# zigbee_iNEMO.net
KiCad netlist of a schematic drawn in EAGLE
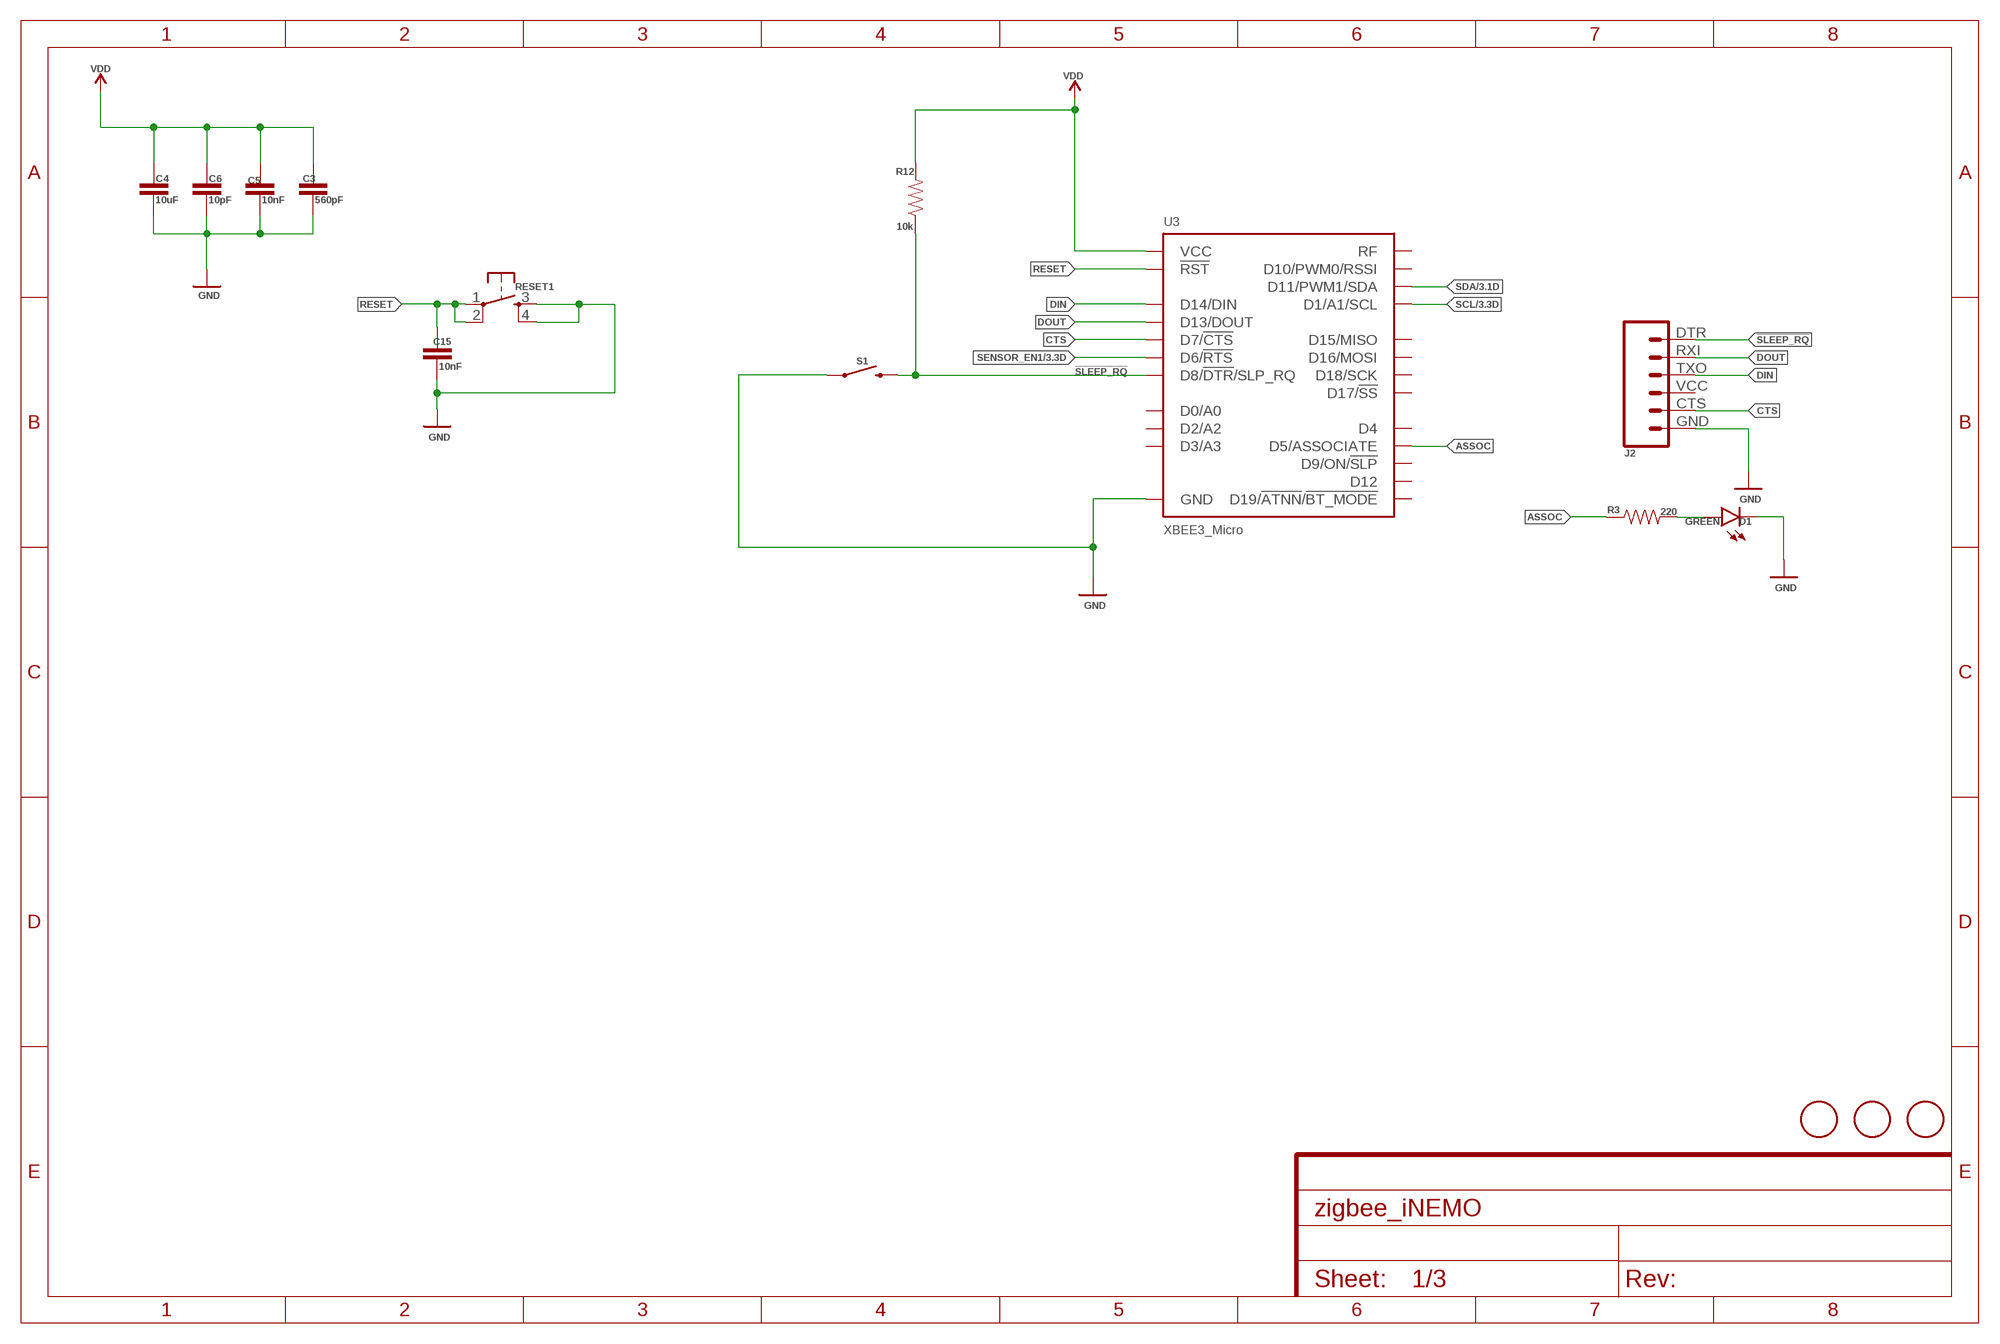
[diagram p0: schematic, sheet 1]
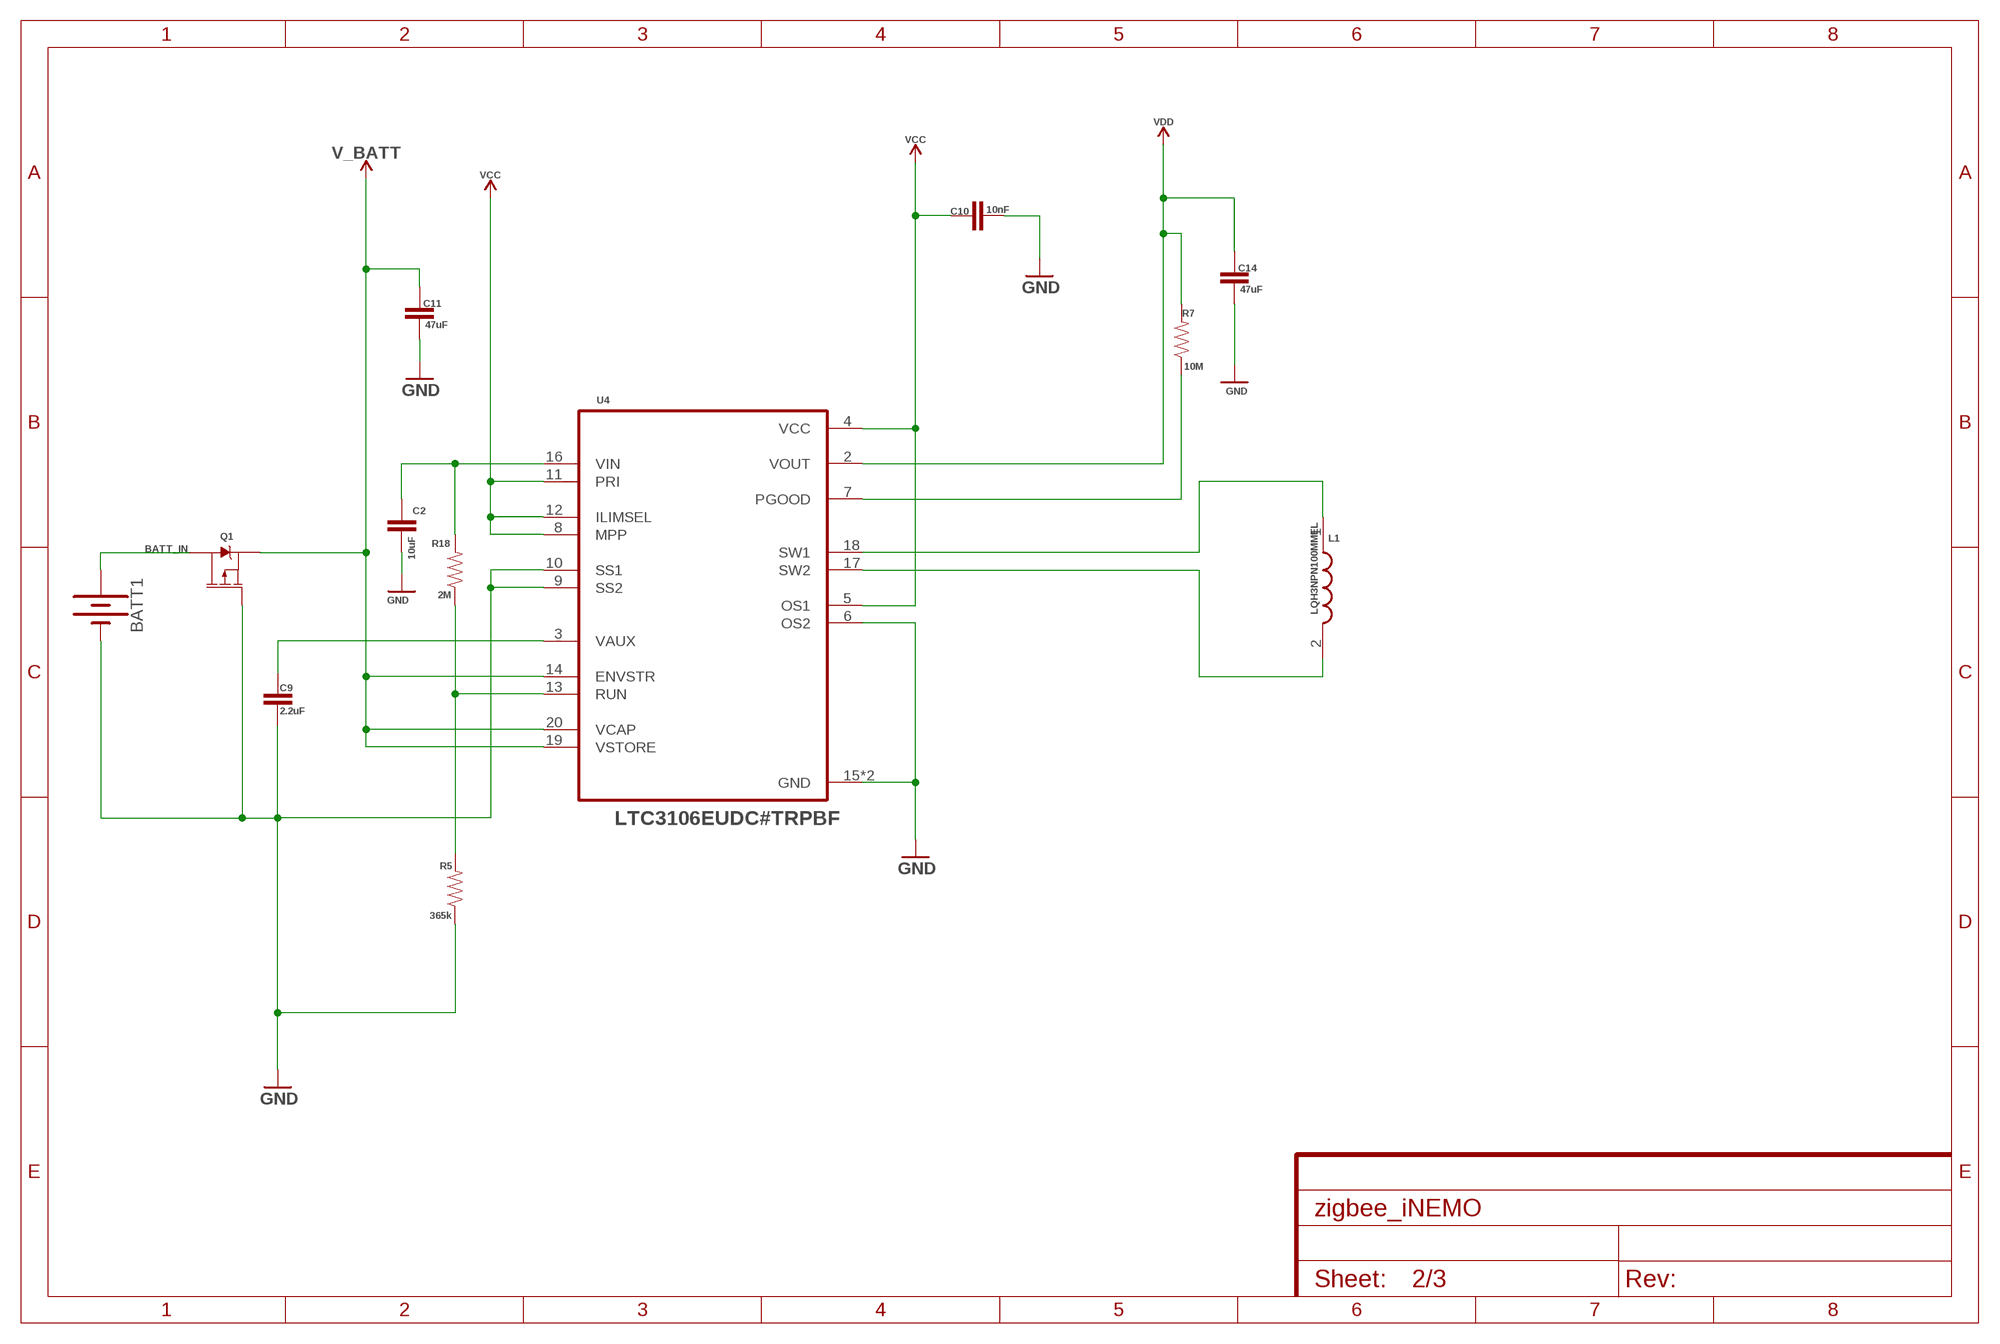
[diagram p1: schematic, sheet 2]
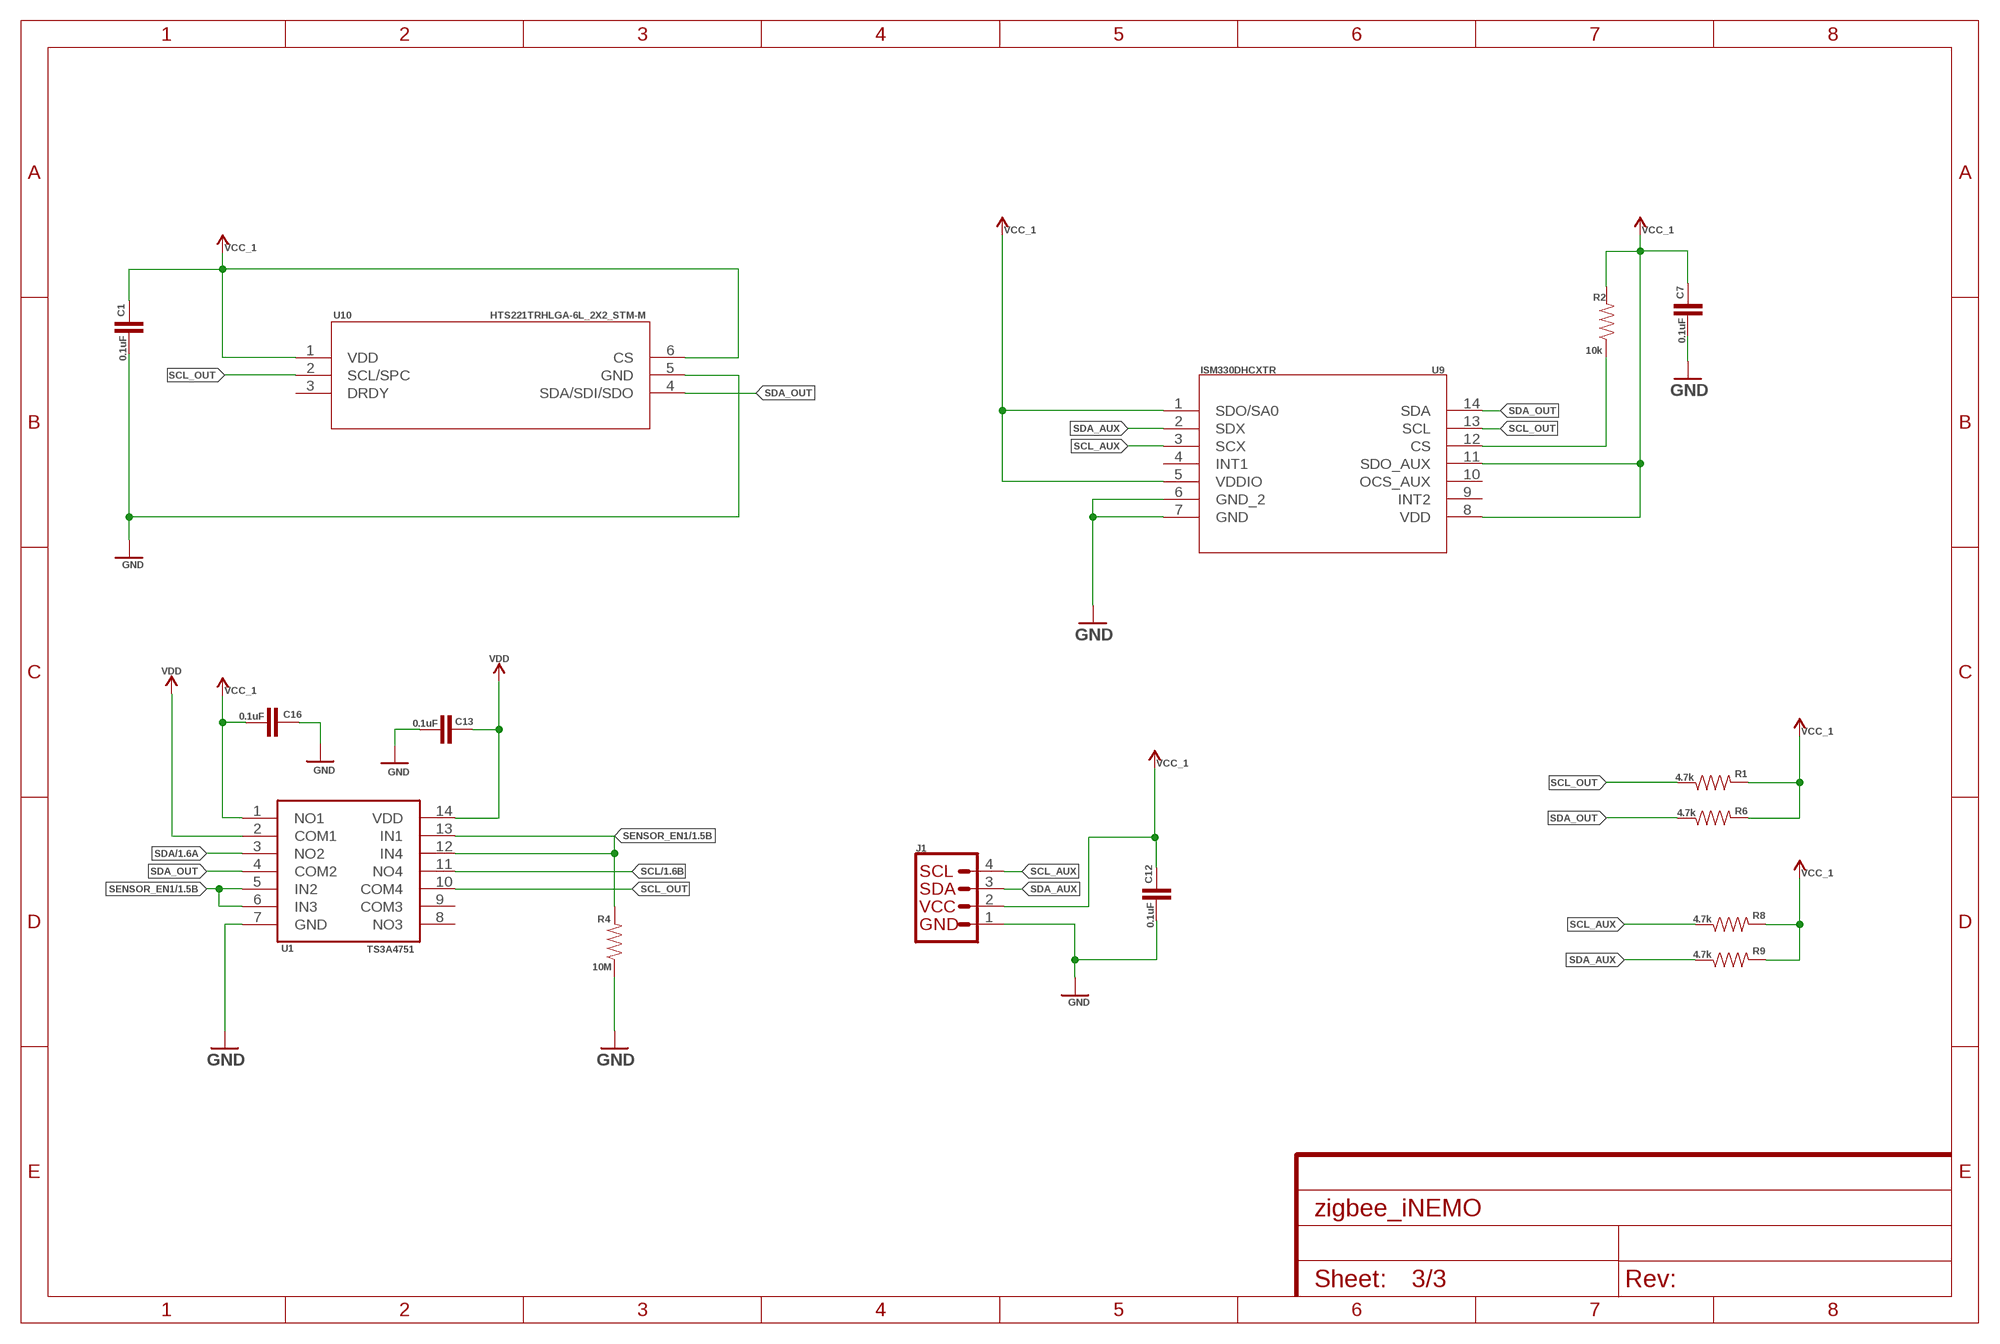
[diagram p2: schematic, sheet 3]

(export (version "E")
  (design (tool "Eeschema 10.0.6"))
  (components
    (comp (ref "BATT1")
      (value "KEYSTONE_54KEYSTONE_2")
      (footprint "eagle-import:KEYSTONE_V2")
      (libsource (lib "eagle-import") (part "KEYSTONE_54KEYSTONE_2"))
    )
    (comp (ref "C2")
      (value "10uF")
      (footprint "eagle-import:0603")
      (libsource (lib "eagle-import") (part "10UF-0603-6.3V-20%"))
    )
    (comp (ref "C9")
      (value "2.2uF")
      (footprint "eagle-import:0603")
      (libsource (lib "eagle-import") (part "2.2UF-0603-10V-20%"))
    )
    (comp (ref "C10")
      (value "10nF")
      (footprint "eagle-import:0603")
      (libsource (lib "eagle-import") (part "10NF-0603-50V-10%"))
    )
    (comp (ref "C11")
      (value "47uF")
      (footprint "eagle-import:0603")
      (libsource (lib "eagle-import") (part "4.7UF0603"))
    )
    (comp (ref "C14")
      (value "47uF")
      (footprint "eagle-import:0603")
      (libsource (lib "eagle-import") (part "4.7UF0603"))
    )
    (comp (ref "L1")
      (value "LQH3NPN100MMEL")
      (footprint "eagle-import:INDPM3030X150N")
      (fields (field (name "MOUSER_PART_NUMBER") "81-LQH3NPN100MMEL"))
      (libsource (lib "eagle-import") (part "LQH3NPN100MMEL"))
    )
    (comp (ref "Q1")
      (value "2.5A/30V/105mΩ")
      (footprint "eagle-import:SOT23-3")
      (libsource (lib "eagle-import") (part "MOSFET_PCH-DMG2307L"))
    )
    (comp (ref "R5")
      (value "365k")
      (footprint "eagle-import:0603")
      (libsource (lib "eagle-import") (part "348KOHM-0603-1/10W-1%"))
    )
    (comp (ref "R7")
      (value "10M")
      (footprint "eagle-import:0603")
      (libsource (lib "eagle-import") (part "10MOHM-0603-1/10W-5%"))
    )
    (comp (ref "R18")
      (value "2M")
      (footprint "eagle-import:0603")
      (libsource (lib "eagle-import") (part "1MOHM-0603-1/4W-5%"))
    )
    (comp (ref "U4")
      (value "LTC3106EUDC#TRPBF")
      (footprint "eagle-import:QFN50P400X300X80-21N")
      (fields (field (name "MF") "Linear Technology/Analog"))
      (libsource (lib "eagle-import") (part "LTC3106EUDC#TRPBF"))
    )
    (comp (ref "C3")
      (value "560pF")
      (footprint "eagle-import:0603")
      (libsource (lib "eagle-import") (part "560PF-0603-50V-5%"))
    )
    (comp (ref "C4")
      (value "10uF")
      (footprint "eagle-import:0603")
      (libsource (lib "eagle-import") (part "10UF-0603-6.3V-20%"))
    )
    (comp (ref "C5")
      (value "10nF")
      (footprint "eagle-import:0603")
      (libsource (lib "eagle-import") (part "10NF-0603-50V-10%"))
    )
    (comp (ref "C6")
      (value "10pF")
      (footprint "eagle-import:0603")
      (libsource (lib "eagle-import") (part "10PF-0603-50V-5%"))
    )
    (comp (ref "C15")
      (value "10nF")
      (footprint "eagle-import:0603")
      (libsource (lib "eagle-import") (part "10NF-0603-50V-10%"))
    )
    (comp (ref "D1")
      (value "GREEN")
      (footprint "eagle-import:LED-0603")
      (libsource (lib "eagle-import") (part "LED-GREEN0603"))
    )
    (comp (ref "J2")
      (value "6_PIN_SERIAL_CABLEPTH")
      (footprint "eagle-import:FTDI_BASIC")
      (libsource (lib "eagle-import") (part "6_PIN_SERIAL_CABLEPTH"))
    )
    (comp (ref "R3")
      (value "220")
      (footprint "eagle-import:0603")
      (libsource (lib "eagle-import") (part "220OHM-0603-1/10W-1%"))
    )
    (comp (ref "R12")
      (value "10k")
      (footprint "eagle-import:0603")
      (libsource (lib "eagle-import") (part "10KOHM-0603-1/10W-1%"))
    )
    (comp (ref "RESET1")
      (value "MOMENTARY-SWITCH-SPST-2-SMD-4.6X2.8MM")
      (footprint "eagle-import:TACTILE_SWITCH_SMD_4.6X2.8MM")
      (libsource (lib "eagle-import") (part "MOMENTARY-SWITCH-SPST-2-SMD-4.6X2.8MM"))
    )
    (comp (ref "S1")
      (value "MOMENTARY-SWITCH-SPST-SMD-4.6X2.8MM")
      (footprint "eagle-import:TACTILE_SWITCH_SMD_4.6X2.8MM")
      (libsource (lib "eagle-import") (part "MOMENTARY-SWITCH-SPST-SMD-4.6X2.8MM"))
    )
    (comp (ref "U$5")
      (value "FIDUCIAL")
      (footprint "eagle-import:FIDUCIAL_1MM")
      (libsource (lib "eagle-import") (part "FIDUCIAL"))
    )
    (comp (ref "U$6")
      (value "FIDUCIAL")
      (footprint "eagle-import:FIDUCIAL_1MM")
      (libsource (lib "eagle-import") (part "FIDUCIAL"))
    )
    (comp (ref "U$7")
      (value "FIDUCIAL")
      (footprint "eagle-import:FIDUCIAL_1MM")
      (libsource (lib "eagle-import") (part "FIDUCIAL"))
    )
    (comp (ref "U3")
      (value "XBEE3_Micro")
      (footprint "eagle-import:XBEE3_THING_PLUS_SPARKFUN-RF_XBEE3")
      (libsource (lib "eagle-import") (part "XBEE3_THING_PLUS_SPARKFUN-RF_XBEE3"))
    )
    (comp (ref "C1")
      (value "0.1uF")
      (footprint "eagle-import:0603")
      (libsource (lib "eagle-import") (part "0.1UF-0603-25V-(+80/-20%)"))
    )
    (comp (ref "C7")
      (value "0.1uF")
      (footprint "eagle-import:0603")
      (libsource (lib "eagle-import") (part "0.1UF-0603-25V-(+80/-20%)"))
    )
    (comp (ref "C12")
      (value "0.1uF")
      (footprint "eagle-import:0603")
      (libsource (lib "eagle-import") (part "0.1UF-0603-25V-(+80/-20%)"))
    )
    (comp (ref "C13")
      (value "0.1uF")
      (footprint "eagle-import:0603")
      (libsource (lib "eagle-import") (part "0.1UF-0603-25V-(+80/-20%)"))
    )
    (comp (ref "C16")
      (value "0.1uF")
      (footprint "eagle-import:0603")
      (libsource (lib "eagle-import") (part "0.1UF-0603-25V-(+80/-20%)"))
    )
    (comp (ref "J1")
      (value "I2C_STANDARD")
      (footprint "eagle-import:1X04")
      (libsource (lib "eagle-import") (part "I2C_STANDARD"))
    )
    (comp (ref "R1")
      (value "4.7k")
      (footprint "eagle-import:0603")
      (libsource (lib "eagle-import") (part "4.7KOHM-0603-1/10W-1%"))
    )
    (comp (ref "R2")
      (value "10k")
      (footprint "eagle-import:0603")
      (libsource (lib "eagle-import") (part "10KOHM-0603-1/10W-1%"))
    )
    (comp (ref "R4")
      (value "10M")
      (footprint "eagle-import:0603")
      (libsource (lib "eagle-import") (part "10MOHM-0603-1/10W-5%"))
    )
    (comp (ref "R6")
      (value "4.7k")
      (footprint "eagle-import:0603")
      (libsource (lib "eagle-import") (part "4.7KOHM-0603-1/10W-1%"))
    )
    (comp (ref "R8")
      (value "4.7k")
      (footprint "eagle-import:0603")
      (libsource (lib "eagle-import") (part "4.7KOHM-0603-1/10W-1%"))
    )
    (comp (ref "R9")
      (value "4.7k")
      (footprint "eagle-import:0603")
      (libsource (lib "eagle-import") (part "4.7KOHM-0603-1/10W-1%"))
    )
    (comp (ref "U1")
      (value "TS3A4751")
      (footprint "eagle-import:14_PIN")
      (fields (field (name "MF") "Texas Instruments"))
      (libsource (lib "eagle-import") (part "TS3A4751"))
    )
    (comp (ref "U9")
      (value "ISM330DHCXTR")
      (footprint "eagle-import:QFN_DHCXTR_STM")
      (fields (field (name "COPYRIGHT") "Copyright (C) 2018 Accelerated Designs. All rights reserved"))
      (libsource (lib "eagle-import") (part "ISM330DHCXTR"))
    )
    (comp (ref "U10")
      (value "HTS221TRHLGA-6L_2X2_STM-M")
      (footprint "eagle-import:HLGA-6L_2X2_STM-M")
      (fields
        (field (name "MANUFACTURER_PART_NUMBER") "HTS221TR")
        (field (name "COPYRIGHT") "Copyright (C) 2018 Accelerated Designs. All rights reserved")
      )
      (libsource (lib "eagle-import") (part "HTS221TRHLGA-6L_2X2_STM-M"))
    )
  )
  (nets
    (net (code "1") (name "ASSOC") (class "Default")
      (node (ref "R3") (pin "1") (pinfunction "1_1") (pintype "passive"))
      (node (ref "U3") (pin "P$26") (pinfunction "D5/ASSOCIATE_P$26") (pintype "bidirectional"))
    )
    (net (code "2") (name "BATT_IN") (class "Default")
      (node (ref "BATT1") (pin "P$1") (pinfunction "+_P$1") (pintype "power_in"))
      (node (ref "BATT1") (pin "P$2") (pinfunction "+_P$2") (pintype "power_in"))
      (node (ref "BATT1") (pin "P$3") (pinfunction "+_P$3") (pintype "power_in"))
      (node (ref "Q1") (pin "3") (pinfunction "D_3") (pintype "bidirectional"))
    )
    (net (code "3") (name "CTS") (class "Default")
      (node (ref "J2") (pin "CTS") (pinfunction "5_CTS") (pintype "passive"))
      (node (ref "U3") (pin "P$24") (pinfunction "D7/~{CTS}_P$24") (pintype "bidirectional"))
    )
    (net (code "4") (name "DIN") (class "Default")
      (node (ref "J2") (pin "TXO") (pinfunction "3_TXO") (pintype "passive"))
      (node (ref "U3") (pin "P$4") (pinfunction "D14/DIN_P$4") (pintype "bidirectional"))
    )
    (net (code "5") (name "DOUT") (class "Default")
      (node (ref "J2") (pin "RXI") (pinfunction "2_RXI") (pintype "passive"))
      (node (ref "U3") (pin "P$3") (pinfunction "D13/DOUT_P$3") (pintype "bidirectional"))
    )
    (net (code "6") (name "GND") (class "Default")
      (node (ref "BATT1") (pin "P$4") (pinfunction "-_P$4") (pintype "power_in"))
      (node (ref "BATT1") (pin "P$5") (pinfunction "-_P$5") (pintype "power_in"))
      (node (ref "BATT1") (pin "P$6") (pinfunction "-_P$6") (pintype "power_in"))
      (node (ref "C1") (pin "2") (pinfunction "2_2") (pintype "passive"))
      (node (ref "C10") (pin "2") (pinfunction "2_2") (pintype "passive"))
      (node (ref "C11") (pin "2") (pinfunction "2_2") (pintype "passive"))
      (node (ref "C12") (pin "2") (pinfunction "2_2") (pintype "passive"))
      (node (ref "C13") (pin "2") (pinfunction "2_2") (pintype "passive"))
      (node (ref "C14") (pin "2") (pinfunction "2_2") (pintype "passive"))
      (node (ref "C15") (pin "1") (pinfunction "1_1") (pintype "passive"))
      (node (ref "C16") (pin "1") (pinfunction "1_1") (pintype "passive"))
      (node (ref "C2") (pin "2") (pinfunction "2_2") (pintype "passive"))
      (node (ref "C3") (pin "1") (pinfunction "1_1") (pintype "passive"))
      (node (ref "C4") (pin "1") (pinfunction "1_1") (pintype "passive"))
      (node (ref "C5") (pin "1") (pinfunction "1_1") (pintype "passive"))
      (node (ref "C6") (pin "1") (pinfunction "1_1") (pintype "passive"))
      (node (ref "C7") (pin "2") (pinfunction "2_2") (pintype "passive"))
      (node (ref "C9") (pin "2") (pinfunction "2_2") (pintype "passive"))
      (node (ref "D1") (pin "C") (pinfunction "C_C") (pintype "passive"))
      (node (ref "J1") (pin "1") (pinfunction "1_1") (pintype "power_in"))
      (node (ref "J2") (pin "GND") (pinfunction "6_GND") (pintype "passive"))
      (node (ref "Q1") (pin "1") (pinfunction "G_1") (pintype "bidirectional"))
      (node (ref "R4") (pin "1") (pinfunction "1_1") (pintype "passive"))
      (node (ref "R5") (pin "1") (pinfunction "1_1") (pintype "passive"))
      (node (ref "RESET1") (pin "3") (pinfunction "3_3") (pintype "passive"))
      (node (ref "RESET1") (pin "4") (pinfunction "4_4") (pintype "passive"))
      (node (ref "S1") (pin "1") (pinfunction "1_1") (pintype "passive"))
      (node (ref "S1") (pin "2") (pinfunction "1_2") (pintype "passive"))
      (node (ref "U1") (pin "7") (pinfunction "GND_7") (pintype "bidirectional"))
      (node (ref "U10") (pin "5") (pinfunction "GND_5") (pintype "passive"))
      (node (ref "U3") (pin "P$1") (pinfunction "GND_P$1") (pintype "bidirectional"))
      (node (ref "U3") (pin "P$10") (pinfunction "GND_P$10") (pintype "bidirectional"))
      (node (ref "U3") (pin "P$12") (pinfunction "GND_P$12") (pintype "bidirectional"))
      (node (ref "U3") (pin "P$21") (pinfunction "GND_P$21") (pintype "bidirectional"))
      (node (ref "U3") (pin "P$32") (pinfunction "GND_P$32") (pintype "bidirectional"))
      (node (ref "U3") (pin "P$34") (pinfunction "GND_P$34") (pintype "bidirectional"))
      (node (ref "U4") (pin "10") (pinfunction "SS1_10") (pintype "input"))
      (node (ref "U4") (pin "15") (pinfunction "GND_15") (pintype "power_in"))
      (node (ref "U4") (pin "21") (pinfunction "GND_21") (pintype "power_in"))
      (node (ref "U4") (pin "6") (pinfunction "OS2_6") (pintype "input"))
      (node (ref "U4") (pin "9") (pinfunction "SS2_9") (pintype "input"))
      (node (ref "U9") (pin "6") (pinfunction "GND_2_6") (pintype "passive"))
      (node (ref "U9") (pin "7") (pinfunction "GND_7") (pintype "passive"))
    )
    (net (code "7") (name "Net-(D1-PadA)") (class "Default")
      (node (ref "D1") (pin "A") (pinfunction "A_A") (pintype "passive"))
      (node (ref "R3") (pin "2") (pinfunction "2_2") (pintype "passive"))
    )
    (net (code "8") (name "Net-(U4-PGOOD)") (class "Default")
      (node (ref "R7") (pin "1") (pinfunction "1_1") (pintype "passive"))
      (node (ref "U4") (pin "7") (pinfunction "PGOOD_7") (pintype "bidirectional"))
    )
    (net (code "9") (name "Net-(U4-RUN)") (class "Default")
      (node (ref "R18") (pin "1") (pinfunction "1_1") (pintype "passive"))
      (node (ref "R5") (pin "2") (pinfunction "2_2") (pintype "passive"))
      (node (ref "U4") (pin "13") (pinfunction "RUN_13") (pintype "input"))
    )
    (net (code "10") (name "Net-(U4-SW1)") (class "Default")
      (node (ref "L1") (pin "1") (pinfunction "1_1") (pintype "bidirectional"))
      (node (ref "U4") (pin "18") (pinfunction "SW1_18") (pintype "bidirectional"))
    )
    (net (code "11") (name "Net-(U4-SW2)") (class "Default")
      (node (ref "L1") (pin "2") (pinfunction "2_2") (pintype "bidirectional"))
      (node (ref "U4") (pin "17") (pinfunction "SW2_17") (pintype "bidirectional"))
    )
    (net (code "12") (name "Net-(U4-VAUX)") (class "Default")
      (node (ref "C9") (pin "1") (pinfunction "1_1") (pintype "passive"))
      (node (ref "U4") (pin "3") (pinfunction "VAUX_3") (pintype "bidirectional"))
    )
    (net (code "13") (name "Net-(U4-VIN)") (class "Default")
      (node (ref "C2") (pin "1") (pinfunction "1_1") (pintype "passive"))
      (node (ref "R18") (pin "2") (pinfunction "2_2") (pintype "passive"))
      (node (ref "U4") (pin "16") (pinfunction "VIN_16") (pintype "input"))
    )
    (net (code "14") (name "Net-(U9-CS)") (class "Default")
      (node (ref "R2") (pin "1") (pinfunction "1_1") (pintype "passive"))
      (node (ref "U9") (pin "12") (pinfunction "CS_12") (pintype "passive"))
    )
    (net (code "15") (name "RESET") (class "Default")
      (node (ref "C15") (pin "2") (pinfunction "2_2") (pintype "passive"))
      (node (ref "RESET1") (pin "1") (pinfunction "1_1") (pintype "passive"))
      (node (ref "RESET1") (pin "2") (pinfunction "2_2") (pintype "passive"))
      (node (ref "U3") (pin "P$6") (pinfunction "~{RST}_P$6") (pintype "input"))
    )
    (net (code "16") (name "SCL") (class "Default")
      (node (ref "U1") (pin "11") (pinfunction "NO4_11") (pintype "bidirectional"))
      (node (ref "U3") (pin "P$30") (pinfunction "D1/A1/SCL_P$30") (pintype "bidirectional"))
    )
    (net (code "17") (name "SCL_AUX") (class "Default")
      (node (ref "J1") (pin "4") (pinfunction "4_4") (pintype "passive"))
      (node (ref "R8") (pin "1") (pinfunction "1_1") (pintype "passive"))
      (node (ref "U9") (pin "3") (pinfunction "SCX_3") (pintype "passive"))
    )
    (net (code "18") (name "SCL_OUT") (class "Default")
      (node (ref "R1") (pin "1") (pinfunction "1_1") (pintype "passive"))
      (node (ref "U1") (pin "10") (pinfunction "COM4_10") (pintype "bidirectional"))
      (node (ref "U10") (pin "2") (pinfunction "SCL/SPC_2") (pintype "passive"))
      (node (ref "U9") (pin "13") (pinfunction "SCL_13") (pintype "passive"))
    )
    (net (code "19") (name "SDA") (class "Default")
      (node (ref "U1") (pin "3") (pinfunction "NO2_3") (pintype "bidirectional"))
      (node (ref "U3") (pin "P$8") (pinfunction "D11/PWM1/SDA_P$8") (pintype "bidirectional"))
    )
    (net (code "20") (name "SDA_AUX") (class "Default")
      (node (ref "J1") (pin "3") (pinfunction "3_3") (pintype "passive"))
      (node (ref "R9") (pin "1") (pinfunction "1_1") (pintype "passive"))
      (node (ref "U9") (pin "2") (pinfunction "SDX_2") (pintype "passive"))
    )
    (net (code "21") (name "SDA_OUT") (class "Default")
      (node (ref "R6") (pin "1") (pinfunction "1_1") (pintype "passive"))
      (node (ref "U1") (pin "4") (pinfunction "COM2_4") (pintype "bidirectional"))
      (node (ref "U10") (pin "4") (pinfunction "SDA/SDI/SDO_4") (pintype "passive"))
      (node (ref "U9") (pin "14") (pinfunction "SDA_14") (pintype "passive"))
    )
    (net (code "22") (name "SENSOR_EN1") (class "Default")
      (node (ref "R4") (pin "2") (pinfunction "2_2") (pintype "passive"))
      (node (ref "U1") (pin "12") (pinfunction "IN4_12") (pintype "bidirectional"))
      (node (ref "U1") (pin "13") (pinfunction "IN1_13") (pintype "bidirectional"))
      (node (ref "U1") (pin "5") (pinfunction "IN2_5") (pintype "bidirectional"))
      (node (ref "U1") (pin "6") (pinfunction "IN3_6") (pintype "bidirectional"))
      (node (ref "U3") (pin "P$27") (pinfunction "D6/~{RTS}_P$27") (pintype "bidirectional"))
    )
    (net (code "23") (name "VCC") (class "Default")
      (node (ref "C10") (pin "1") (pinfunction "1_1") (pintype "passive"))
      (node (ref "U4") (pin "11") (pinfunction "PRI_11") (pintype "input"))
      (node (ref "U4") (pin "12") (pinfunction "ILIMSEL_12") (pintype "input"))
      (node (ref "U4") (pin "4") (pinfunction "VCC_4") (pintype "power_in"))
      (node (ref "U4") (pin "5") (pinfunction "OS1_5") (pintype "input"))
      (node (ref "U4") (pin "8") (pinfunction "MPP_8") (pintype "input"))
    )
    (net (code "24") (name "VCC_1") (class "Default")
      (node (ref "C1") (pin "1") (pinfunction "1_1") (pintype "passive"))
      (node (ref "C12") (pin "1") (pinfunction "1_1") (pintype "passive"))
      (node (ref "C16") (pin "2") (pinfunction "2_2") (pintype "passive"))
      (node (ref "C7") (pin "1") (pinfunction "1_1") (pintype "passive"))
      (node (ref "J1") (pin "2") (pinfunction "2_2") (pintype "power_in"))
      (node (ref "R1") (pin "2") (pinfunction "2_2") (pintype "passive"))
      (node (ref "R2") (pin "2") (pinfunction "2_2") (pintype "passive"))
      (node (ref "R6") (pin "2") (pinfunction "2_2") (pintype "passive"))
      (node (ref "R8") (pin "2") (pinfunction "2_2") (pintype "passive"))
      (node (ref "R9") (pin "2") (pinfunction "2_2") (pintype "passive"))
      (node (ref "U1") (pin "1") (pinfunction "NO1_1") (pintype "bidirectional"))
      (node (ref "U10") (pin "1") (pinfunction "VDD_1") (pintype "power_in"))
      (node (ref "U10") (pin "6") (pinfunction "CS_6") (pintype "passive"))
      (node (ref "U9") (pin "1") (pinfunction "SDO/SA0_1") (pintype "passive"))
      (node (ref "U9") (pin "11") (pinfunction "SDO_AUX_11") (pintype "passive"))
      (node (ref "U9") (pin "5") (pinfunction "VDDIO_5") (pintype "power_in"))
      (node (ref "U9") (pin "8") (pinfunction "VDD_8") (pintype "power_in"))
    )
    (net (code "25") (name "VDD") (class "Default")
      (node (ref "C13") (pin "1") (pinfunction "1_1") (pintype "passive"))
      (node (ref "C14") (pin "1") (pinfunction "1_1") (pintype "passive"))
      (node (ref "C3") (pin "2") (pinfunction "2_2") (pintype "passive"))
      (node (ref "C4") (pin "2") (pinfunction "2_2") (pintype "passive"))
      (node (ref "C5") (pin "2") (pinfunction "2_2") (pintype "passive"))
      (node (ref "C6") (pin "2") (pinfunction "2_2") (pintype "passive"))
      (node (ref "R12") (pin "2") (pinfunction "2_2") (pintype "passive"))
      (node (ref "R7") (pin "2") (pinfunction "2_2") (pintype "passive"))
      (node (ref "U1") (pin "14") (pinfunction "VDD_14") (pintype "bidirectional"))
      (node (ref "U1") (pin "2") (pinfunction "COM1_2") (pintype "bidirectional"))
      (node (ref "U3") (pin "P$2") (pinfunction "VCC_P$2") (pintype "bidirectional"))
      (node (ref "U4") (pin "2") (pinfunction "VOUT_2") (pintype "output"))
    )
    (net (code "26") (name "V_BATT") (class "Default")
      (node (ref "C11") (pin "1") (pinfunction "1_1") (pintype "passive"))
      (node (ref "Q1") (pin "2") (pinfunction "S_2") (pintype "bidirectional"))
      (node (ref "U4") (pin "14") (pinfunction "ENVSTR_14") (pintype "input"))
      (node (ref "U4") (pin "19") (pinfunction "VSTORE_19") (pintype "bidirectional"))
      (node (ref "U4") (pin "20") (pinfunction "VCAP_20") (pintype "bidirectional"))
    )
    (net (code "27") (name "unconnected-(J2-4-PadVCC)") (class "Default")
      (node (ref "J2") (pin "VCC") (pinfunction "4_VCC") (pintype "passive"))
    )
    (net (code "28") (name "unconnected-(U1-COM3-Pad9)") (class "Default")
      (node (ref "U1") (pin "9") (pinfunction "COM3_9") (pintype "bidirectional"))
    )
    (net (code "29") (name "unconnected-(U1-NO3-Pad8)") (class "Default")
      (node (ref "U1") (pin "8") (pinfunction "NO3_8") (pintype "bidirectional"))
    )
    (net (code "30") (name "unconnected-(U3-D0{slash}A0-PadP$31)") (class "Default")
      (node (ref "U3") (pin "P$31") (pinfunction "D0/A0_P$31") (pintype "bidirectional"))
    )
    (net (code "31") (name "unconnected-(U3-D2{slash}A2-PadP$29)") (class "Default")
      (node (ref "U3") (pin "P$29") (pinfunction "D2/A2_P$29") (pintype "bidirectional"))
    )
    (net (code "32") (name "unconnected-(U3-D3{slash}A3-PadP$28)") (class "Default")
      (node (ref "U3") (pin "P$28") (pinfunction "D3/A3_P$28") (pintype "bidirectional"))
    )
    (net (code "33") (name "unconnected-(U3-D4-PadP$23)") (class "Default")
      (node (ref "U3") (pin "P$23") (pinfunction "D4_P$23") (pintype "bidirectional"))
    )
    (net (code "34") (name "unconnected-(U3-D9{slash}ON{slash}~{SLP}-PadP$25)") (class "Default")
      (node (ref "U3") (pin "P$25") (pinfunction "D9/ON/~{SLP}_P$25") (pintype "bidirectional"))
    )
    (net (code "35") (name "unconnected-(U3-D10{slash}PWM0{slash}RSSI-PadP$7)") (class "Default")
      (node (ref "U3") (pin "P$7") (pinfunction "D10/PWM0/RSSI_P$7") (pintype "bidirectional"))
    )
    (net (code "36") (name "unconnected-(U3-D12-PadP$5)") (class "Default")
      (node (ref "U3") (pin "P$5") (pinfunction "D12_P$5") (pintype "bidirectional"))
    )
    (net (code "37") (name "unconnected-(U3-D15{slash}MISO-PadP$16)") (class "Default")
      (node (ref "U3") (pin "P$16") (pinfunction "D15/MISO_P$16") (pintype "bidirectional"))
    )
    (net (code "38") (name "unconnected-(U3-D16{slash}MOSI-PadP$15)") (class "Default")
      (node (ref "U3") (pin "P$15") (pinfunction "D16/MOSI_P$15") (pintype "bidirectional"))
    )
    (net (code "39") (name "unconnected-(U3-D17{slash}~{SS}-PadP$14)") (class "Default")
      (node (ref "U3") (pin "P$14") (pinfunction "D17/~{SS}_P$14") (pintype "bidirectional"))
    )
    (net (code "40") (name "unconnected-(U3-D18{slash}SCK-PadP$13)") (class "Default")
      (node (ref "U3") (pin "P$13") (pinfunction "D18/SCK_P$13") (pintype "bidirectional"))
    )
    (net (code "41") (name "unconnected-(U3-D19{slash}~{ATNN}{slash}~{BT_MODE}-PadP$11)") (class "Default")
      (node (ref "U3") (pin "P$11") (pinfunction "D19/~{ATNN}/~{BT_MODE}_P$11") (pintype "bidirectional"))
    )
    (net (code "42") (name "unconnected-(U3-RF-PadP$33)") (class "Default")
      (node (ref "U3") (pin "P$33") (pinfunction "RF_P$33") (pintype "bidirectional"))
    )
    (net (code "43") (name "unconnected-(U9-INT1-Pad4)") (class "Default")
      (node (ref "U9") (pin "4") (pinfunction "INT1_4") (pintype "input"))
    )
    (net (code "44") (name "unconnected-(U9-INT2-Pad9)") (class "Default")
      (node (ref "U9") (pin "9") (pinfunction "INT2_9") (pintype "input"))
    )
    (net (code "45") (name "unconnected-(U9-OCS_AUX-Pad10)") (class "Default")
      (node (ref "U9") (pin "10") (pinfunction "OCS_AUX_10") (pintype "passive"))
    )
    (net (code "46") (name "unconnected-(U10-DRDY-Pad3)") (class "Default")
      (node (ref "U10") (pin "3") (pinfunction "DRDY_3") (pintype "passive"))
    )
    (net (code "47") (name "~{SLEEP_RQ}") (class "Default")
      (node (ref "J2") (pin "DTR") (pinfunction "1_DTR") (pintype "passive"))
      (node (ref "R12") (pin "1") (pinfunction "1_1") (pintype "passive"))
      (node (ref "S1") (pin "3") (pinfunction "2_3") (pintype "passive"))
      (node (ref "S1") (pin "4") (pinfunction "2_4") (pintype "passive"))
      (node (ref "U3") (pin "P$9") (pinfunction "D8/~{DTR}/SLP_RQ_P$9") (pintype "bidirectional"))
    )
  )
)
